# rpiz_test.net
KiCad netlist of a schematic drawn in EAGLE
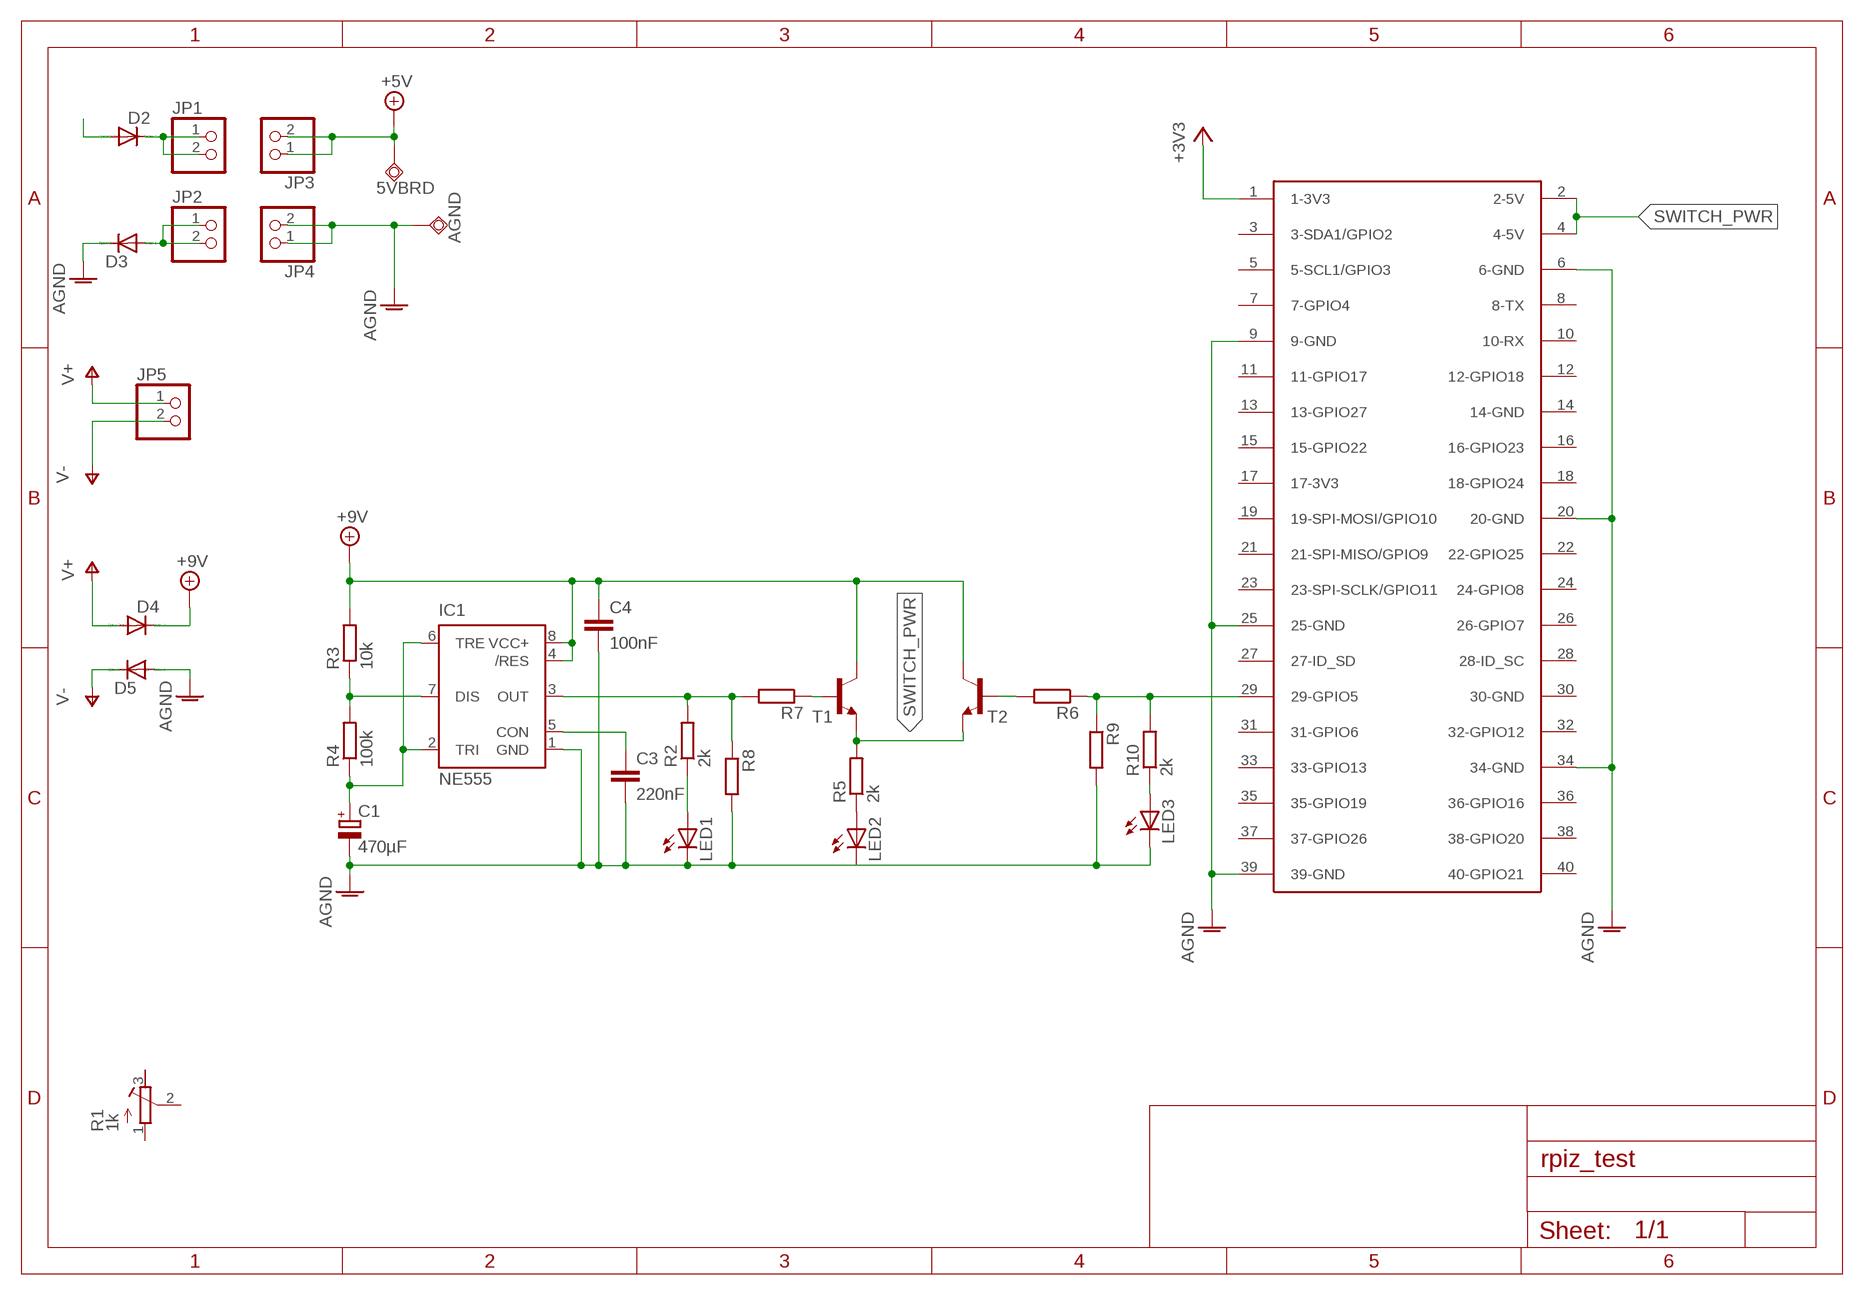
[diagram p0: schematic, sheet 1]

(export (version "E")
  (design (tool "Eeschema 10.0.6"))
  (components
    (comp (ref "5VBRD")
      (value "TPSQTP20SQ")
      (footprint "eagle-import:TP20SQ")
      (libsource (lib "eagle-import") (part "TPSQTP20SQ"))
    )
    (comp (ref "AGND")
      (value "TPSQTP20SQ")
      (footprint "eagle-import:TP20SQ")
      (libsource (lib "eagle-import") (part "TPSQTP20SQ"))
    )
    (comp (ref "C1")
      (value "470µF")
      (footprint "eagle-import:E5-10,5")
      (libsource (lib "eagle-import") (part "CPOL-EUE5-10.5"))
    )
    (comp (ref "C3")
      (value "220nF")
      (footprint "eagle-import:C050-030X075")
      (libsource (lib "eagle-import") (part "C-EU050-030X075"))
    )
    (comp (ref "C4")
      (value "100nF")
      (footprint "eagle-import:C050-030X075")
      (libsource (lib "eagle-import") (part "C-EU050-030X075"))
    )
    (comp (ref "D2")
      (value "1N4148DO35-7")
      (footprint "eagle-import:DO35-7")
      (libsource (lib "eagle-import") (part "1N4148DO35-7"))
    )
    (comp (ref "D3")
      (value "1N4148DO35-7")
      (footprint "eagle-import:DO35-7")
      (libsource (lib "eagle-import") (part "1N4148DO35-7"))
    )
    (comp (ref "D4")
      (value "1N4148DO35-7")
      (footprint "eagle-import:DO35-7")
      (libsource (lib "eagle-import") (part "1N4148DO35-7"))
    )
    (comp (ref "D5")
      (value "1N4148DO35-7")
      (footprint "eagle-import:DO35-7")
      (libsource (lib "eagle-import") (part "1N4148DO35-7"))
    )
    (comp (ref "IC1")
      (value "NE555")
      (footprint "eagle-import:DIL-08")
      (fields (field (name "MF") "Arrow Electronics") (field (name "MPN") "NE555N"))
      (libsource (lib "eagle-import") (part "NE555"))
    )
    (comp (ref "JP1")
      (value "PINHD-1X2")
      (footprint "eagle-import:1X02")
      (libsource (lib "eagle-import") (part "PINHD-1X2"))
    )
    (comp (ref "JP2")
      (value "PINHD-1X2")
      (footprint "eagle-import:1X02")
      (libsource (lib "eagle-import") (part "PINHD-1X2"))
    )
    (comp (ref "JP3")
      (value "PINHD-1X2")
      (footprint "eagle-import:1X02")
      (libsource (lib "eagle-import") (part "PINHD-1X2"))
    )
    (comp (ref "JP4")
      (value "PINHD-1X2")
      (footprint "eagle-import:1X02")
      (libsource (lib "eagle-import") (part "PINHD-1X2"))
    )
    (comp (ref "JP5")
      (value "PINHD-1X2")
      (footprint "eagle-import:1X02")
      (libsource (lib "eagle-import") (part "PINHD-1X2"))
    )
    (comp (ref "LED1")
      (value "LED5MM")
      (footprint "eagle-import:LED5MM")
      (libsource (lib "eagle-import") (part "LED5MM"))
    )
    (comp (ref "LED2")
      (value "LED5MM")
      (footprint "eagle-import:LED5MM")
      (libsource (lib "eagle-import") (part "LED5MM"))
    )
    (comp (ref "LED3")
      (value "LED5MM")
      (footprint "eagle-import:LED5MM")
      (libsource (lib "eagle-import") (part "LED5MM"))
    )
    (comp (ref "R1")
      (value "1k")
      (footprint "eagle-import:RTRIM64W")
      (libsource (lib "eagle-import") (part "R-TRIMM64W"))
    )
    (comp (ref "R2")
      (value "2k")
      (footprint "eagle-import:0207_10")
      (libsource (lib "eagle-import") (part "R-EU_0207/10"))
    )
    (comp (ref "R3")
      (value "10k")
      (footprint "eagle-import:0207_10")
      (libsource (lib "eagle-import") (part "R-EU_0207/10"))
    )
    (comp (ref "R4")
      (value "100k")
      (footprint "eagle-import:0207_10")
      (libsource (lib "eagle-import") (part "R-EU_0207/10"))
    )
    (comp (ref "R5")
      (value "2k")
      (footprint "eagle-import:0207_10")
      (libsource (lib "eagle-import") (part "R-EU_0207/10"))
    )
    (comp (ref "R6")
      (value "R-EU_R0805")
      (footprint "eagle-import:R0805")
      (libsource (lib "eagle-import") (part "R-EU_R0805"))
    )
    (comp (ref "R7")
      (value "R-EU_R0805")
      (footprint "eagle-import:R0805")
      (libsource (lib "eagle-import") (part "R-EU_R0805"))
    )
    (comp (ref "R8")
      (value "R-EU_R0805")
      (footprint "eagle-import:R0805")
      (libsource (lib "eagle-import") (part "R-EU_R0805"))
    )
    (comp (ref "R9")
      (value "R-EU_R0805")
      (footprint "eagle-import:R0805")
      (libsource (lib "eagle-import") (part "R-EU_R0805"))
    )
    (comp (ref "R10")
      (value "2k")
      (footprint "eagle-import:0207_10")
      (libsource (lib "eagle-import") (part "R-EU_0207/10"))
    )
    (comp (ref "T1")
      (value "BC547-NPN-TO92-CBE")
      (footprint "eagle-import:TO92-CBE")
      (libsource (lib "eagle-import") (part "-NPN-TO92-CBEBC547"))
    )
    (comp (ref "T2")
      (value "BC547-NPN-TO92-CBE")
      (footprint "eagle-import:TO92-CBE")
      (libsource (lib "eagle-import") (part "-NPN-TO92-CBEBC547"))
    )
    (comp (ref "U$1")
      (value "RASPBERRY-PI+PIZERO")
      (footprint "eagle-import:RASPBERRY-PI-ZERO")
      (libsource (lib "eagle-import") (part "RASPBERRY-PI+PIZERO"))
    )
  )
  (nets
    (net (code "1") (name "+3V3") (class "Default")
      (node (ref "U$1") (pin "1") (pinfunction "1-3V3_1") (pintype "bidirectional"))
    )
    (net (code "2") (name "+5V") (class "Default")
      (node (ref "5VBRD") (pin "TP") (pinfunction "TP_TP") (pintype "input"))
      (node (ref "JP3") (pin "1") (pinfunction "1_1") (pintype "passive"))
      (node (ref "JP3") (pin "2") (pinfunction "2_2") (pintype "passive"))
    )
    (net (code "3") (name "+9V") (class "Default")
      (node (ref "C4") (pin "1") (pinfunction "1_1") (pintype "passive"))
      (node (ref "D4") (pin "C") (pinfunction "C_C") (pintype "passive"))
      (node (ref "IC1") (pin "4") (pinfunction "/RES_4") (pintype "input"))
      (node (ref "IC1") (pin "8") (pinfunction "VCC+_8") (pintype "power_in"))
      (node (ref "R3") (pin "2") (pinfunction "2_2") (pintype "passive"))
      (node (ref "T1") (pin "C") (pinfunction "C_C") (pintype "passive"))
      (node (ref "T2") (pin "C") (pinfunction "C_C") (pintype "passive"))
    )
    (net (code "4") (name "AGND") (class "Default")
      (node (ref "AGND") (pin "TP") (pinfunction "TP_TP") (pintype "input"))
      (node (ref "C1") (pin "-") (pinfunction "-_-") (pintype "passive"))
      (node (ref "C3") (pin "2") (pinfunction "2_2") (pintype "passive"))
      (node (ref "C4") (pin "2") (pinfunction "2_2") (pintype "passive"))
      (node (ref "D3") (pin "C") (pinfunction "C_C") (pintype "passive"))
      (node (ref "D5") (pin "A") (pinfunction "A_A") (pintype "passive"))
      (node (ref "IC1") (pin "1") (pinfunction "GND_1") (pintype "power_in"))
      (node (ref "JP4") (pin "1") (pinfunction "1_1") (pintype "passive"))
      (node (ref "JP4") (pin "2") (pinfunction "2_2") (pintype "passive"))
      (node (ref "LED1") (pin "K") (pinfunction "C_K") (pintype "passive"))
      (node (ref "LED2") (pin "K") (pinfunction "C_K") (pintype "passive"))
      (node (ref "LED3") (pin "K") (pinfunction "C_K") (pintype "passive"))
      (node (ref "R8") (pin "2") (pinfunction "2_2") (pintype "passive"))
      (node (ref "R9") (pin "2") (pinfunction "2_2") (pintype "passive"))
      (node (ref "U$1") (pin "20") (pinfunction "20-GND_20") (pintype "bidirectional"))
      (node (ref "U$1") (pin "25") (pinfunction "25-GND_25") (pintype "bidirectional"))
      (node (ref "U$1") (pin "34") (pinfunction "34-GND_34") (pintype "bidirectional"))
      (node (ref "U$1") (pin "39") (pinfunction "39-GND_39") (pintype "bidirectional"))
      (node (ref "U$1") (pin "6") (pinfunction "6-GND_6") (pintype "bidirectional"))
      (node (ref "U$1") (pin "9") (pinfunction "9-GND_9") (pintype "bidirectional"))
    )
    (net (code "5") (name "Net-(D2-PadC)") (class "Default")
      (node (ref "D2") (pin "C") (pinfunction "C_C") (pintype "passive"))
      (node (ref "JP1") (pin "1") (pinfunction "1_1") (pintype "passive"))
      (node (ref "JP1") (pin "2") (pinfunction "2_2") (pintype "passive"))
    )
    (net (code "6") (name "Net-(D3-PadA)") (class "Default")
      (node (ref "D3") (pin "A") (pinfunction "A_A") (pintype "passive"))
      (node (ref "JP2") (pin "1") (pinfunction "1_1") (pintype "passive"))
      (node (ref "JP2") (pin "2") (pinfunction "2_2") (pintype "passive"))
    )
    (net (code "7") (name "Net-(IC1-CON)") (class "Default")
      (node (ref "C3") (pin "1") (pinfunction "1_1") (pintype "passive"))
      (node (ref "IC1") (pin "5") (pinfunction "CON_5") (pintype "input"))
    )
    (net (code "8") (name "Net-(IC1-DIS)") (class "Default")
      (node (ref "IC1") (pin "7") (pinfunction "DIS_7") (pintype "input"))
      (node (ref "R3") (pin "1") (pinfunction "1_1") (pintype "passive"))
      (node (ref "R4") (pin "2") (pinfunction "2_2") (pintype "passive"))
    )
    (net (code "9") (name "Net-(IC1-OUT)") (class "Default")
      (node (ref "IC1") (pin "3") (pinfunction "OUT_3") (pintype "output"))
      (node (ref "R2") (pin "2") (pinfunction "2_2") (pintype "passive"))
      (node (ref "R7") (pin "2") (pinfunction "2_2") (pintype "passive"))
      (node (ref "R8") (pin "1") (pinfunction "1_1") (pintype "passive"))
    )
    (net (code "10") (name "Net-(IC1-TRE)") (class "Default")
      (node (ref "C1") (pin "+") (pinfunction "+_+") (pintype "passive"))
      (node (ref "IC1") (pin "2") (pinfunction "TRI_2") (pintype "input"))
      (node (ref "IC1") (pin "6") (pinfunction "TRE_6") (pintype "input"))
      (node (ref "R4") (pin "1") (pinfunction "1_1") (pintype "passive"))
    )
    (net (code "11") (name "Net-(LED1-PadA)") (class "Default")
      (node (ref "LED1") (pin "A") (pinfunction "A_A") (pintype "passive"))
      (node (ref "R2") (pin "1") (pinfunction "1_1") (pintype "passive"))
    )
    (net (code "12") (name "Net-(LED2-PadA)") (class "Default")
      (node (ref "LED2") (pin "A") (pinfunction "A_A") (pintype "passive"))
      (node (ref "R5") (pin "1") (pinfunction "1_1") (pintype "passive"))
    )
    (net (code "13") (name "Net-(LED3-PadA)") (class "Default")
      (node (ref "LED3") (pin "A") (pinfunction "A_A") (pintype "passive"))
      (node (ref "R10") (pin "1") (pinfunction "1_1") (pintype "passive"))
    )
    (net (code "14") (name "Net-(R6-Pad2)") (class "Default")
      (node (ref "R6") (pin "2") (pinfunction "2_2") (pintype "passive"))
      (node (ref "T2") (pin "B") (pinfunction "B_B") (pintype "passive"))
    )
    (net (code "15") (name "Net-(R7-Pad1)") (class "Default")
      (node (ref "R7") (pin "1") (pinfunction "1_1") (pintype "passive"))
      (node (ref "T1") (pin "B") (pinfunction "B_B") (pintype "passive"))
    )
    (net (code "16") (name "Net-(U$1-29-GPIO5)") (class "Default")
      (node (ref "R10") (pin "2") (pinfunction "2_2") (pintype "passive"))
      (node (ref "R6") (pin "1") (pinfunction "1_1") (pintype "passive"))
      (node (ref "R9") (pin "1") (pinfunction "1_1") (pintype "passive"))
      (node (ref "U$1") (pin "29") (pinfunction "29-GPIO5_29") (pintype "bidirectional"))
    )
    (net (code "17") (name "SWITCH_PWR") (class "Default")
      (node (ref "R5") (pin "2") (pinfunction "2_2") (pintype "passive"))
      (node (ref "T1") (pin "E") (pinfunction "E_E") (pintype "passive"))
      (node (ref "T2") (pin "E") (pinfunction "E_E") (pintype "passive"))
      (node (ref "U$1") (pin "2") (pinfunction "2-5V_2") (pintype "bidirectional"))
      (node (ref "U$1") (pin "4") (pinfunction "4-5V_4") (pintype "bidirectional"))
    )
    (net (code "18") (name "V+") (class "Default")
      (node (ref "D4") (pin "A") (pinfunction "A_A") (pintype "passive"))
      (node (ref "JP5") (pin "1") (pinfunction "1_1") (pintype "passive"))
    )
    (net (code "19") (name "V-") (class "Default")
      (node (ref "D5") (pin "C") (pinfunction "C_C") (pintype "passive"))
      (node (ref "JP5") (pin "2") (pinfunction "2_2") (pintype "passive"))
    )
    (net (code "20") (name "unconnected-(D2-PadA)") (class "Default")
      (node (ref "D2") (pin "A") (pinfunction "A_A") (pintype "passive"))
    )
    (net (code "21") (name "unconnected-(R1-A-Pad1)") (class "Default")
      (node (ref "R1") (pin "1") (pinfunction "A_1") (pintype "passive"))
    )
    (net (code "22") (name "unconnected-(R1-E-Pad3)") (class "Default")
      (node (ref "R1") (pin "3") (pinfunction "E_3") (pintype "passive"))
    )
    (net (code "23") (name "unconnected-(R1-S-Pad2)") (class "Default")
      (node (ref "R1") (pin "2") (pinfunction "S_2") (pintype "passive"))
    )
    (net (code "24") (name "unconnected-(U$1-3-SDA1{slash}GPIO2-Pad3)") (class "Default")
      (node (ref "U$1") (pin "3") (pinfunction "3-SDA1/GPIO2_3") (pintype "bidirectional"))
    )
    (net (code "25") (name "unconnected-(U$1-5-SCL1{slash}GPIO3-Pad5)") (class "Default")
      (node (ref "U$1") (pin "5") (pinfunction "5-SCL1/GPIO3_5") (pintype "bidirectional"))
    )
    (net (code "26") (name "unconnected-(U$1-7-GPIO4-Pad7)") (class "Default")
      (node (ref "U$1") (pin "7") (pinfunction "7-GPIO4_7") (pintype "bidirectional"))
    )
    (net (code "27") (name "unconnected-(U$1-8-TX-Pad8)") (class "Default")
      (node (ref "U$1") (pin "8") (pinfunction "8-TX_8") (pintype "bidirectional"))
    )
    (net (code "28") (name "unconnected-(U$1-10-RX-Pad10)") (class "Default")
      (node (ref "U$1") (pin "10") (pinfunction "10-RX_10") (pintype "bidirectional"))
    )
    (net (code "29") (name "unconnected-(U$1-11-GPIO17-Pad11)") (class "Default")
      (node (ref "U$1") (pin "11") (pinfunction "11-GPIO17_11") (pintype "bidirectional"))
    )
    (net (code "30") (name "unconnected-(U$1-12-GPIO18-Pad12)") (class "Default")
      (node (ref "U$1") (pin "12") (pinfunction "12-GPIO18_12") (pintype "bidirectional"))
    )
    (net (code "31") (name "unconnected-(U$1-13-GPIO27-Pad13)") (class "Default")
      (node (ref "U$1") (pin "13") (pinfunction "13-GPIO27_13") (pintype "bidirectional"))
    )
    (net (code "32") (name "unconnected-(U$1-14-GND-Pad14)") (class "Default")
      (node (ref "U$1") (pin "14") (pinfunction "14-GND_14") (pintype "bidirectional"))
    )
    (net (code "33") (name "unconnected-(U$1-15-GPIO22-Pad15)") (class "Default")
      (node (ref "U$1") (pin "15") (pinfunction "15-GPIO22_15") (pintype "bidirectional"))
    )
    (net (code "34") (name "unconnected-(U$1-16-GPIO23-Pad16)") (class "Default")
      (node (ref "U$1") (pin "16") (pinfunction "16-GPIO23_16") (pintype "bidirectional"))
    )
    (net (code "35") (name "unconnected-(U$1-17-3V3-Pad17)") (class "Default")
      (node (ref "U$1") (pin "17") (pinfunction "17-3V3_17") (pintype "bidirectional"))
    )
    (net (code "36") (name "unconnected-(U$1-18-GPIO24-Pad18)") (class "Default")
      (node (ref "U$1") (pin "18") (pinfunction "18-GPIO24_18") (pintype "bidirectional"))
    )
    (net (code "37") (name "unconnected-(U$1-19-SPI-MOSI{slash}GPIO10-Pad19)") (class "Default")
      (node (ref "U$1") (pin "19") (pinfunction "19-SPI-MOSI/GPIO10_19") (pintype "bidirectional"))
    )
    (net (code "38") (name "unconnected-(U$1-21-SPI-MISO{slash}GPIO9-Pad21)") (class "Default")
      (node (ref "U$1") (pin "21") (pinfunction "21-SPI-MISO/GPIO9_21") (pintype "bidirectional"))
    )
    (net (code "39") (name "unconnected-(U$1-22-GPIO25-Pad22)") (class "Default")
      (node (ref "U$1") (pin "22") (pinfunction "22-GPIO25_22") (pintype "bidirectional"))
    )
    (net (code "40") (name "unconnected-(U$1-23-SPI-SCLK{slash}GPIO11-Pad23)") (class "Default")
      (node (ref "U$1") (pin "23") (pinfunction "23-SPI-SCLK/GPIO11_23") (pintype "bidirectional"))
    )
    (net (code "41") (name "unconnected-(U$1-24-GPIO8-Pad24)") (class "Default")
      (node (ref "U$1") (pin "24") (pinfunction "24-GPIO8_24") (pintype "bidirectional"))
    )
    (net (code "42") (name "unconnected-(U$1-26-GPIO7-Pad26)") (class "Default")
      (node (ref "U$1") (pin "26") (pinfunction "26-GPIO7_26") (pintype "bidirectional"))
    )
    (net (code "43") (name "unconnected-(U$1-27-ID_SD-Pad27)") (class "Default")
      (node (ref "U$1") (pin "27") (pinfunction "27-ID_SD_27") (pintype "bidirectional"))
    )
    (net (code "44") (name "unconnected-(U$1-28-ID_SC-Pad28)") (class "Default")
      (node (ref "U$1") (pin "28") (pinfunction "28-ID_SC_28") (pintype "bidirectional"))
    )
    (net (code "45") (name "unconnected-(U$1-30-GND-Pad30)") (class "Default")
      (node (ref "U$1") (pin "30") (pinfunction "30-GND_30") (pintype "bidirectional"))
    )
    (net (code "46") (name "unconnected-(U$1-31-GPIO6-Pad31)") (class "Default")
      (node (ref "U$1") (pin "31") (pinfunction "31-GPIO6_31") (pintype "bidirectional"))
    )
    (net (code "47") (name "unconnected-(U$1-32-GPIO12-Pad32)") (class "Default")
      (node (ref "U$1") (pin "32") (pinfunction "32-GPIO12_32") (pintype "bidirectional"))
    )
    (net (code "48") (name "unconnected-(U$1-33-GPIO13-Pad33)") (class "Default")
      (node (ref "U$1") (pin "33") (pinfunction "33-GPIO13_33") (pintype "bidirectional"))
    )
    (net (code "49") (name "unconnected-(U$1-35-GPIO19-Pad35)") (class "Default")
      (node (ref "U$1") (pin "35") (pinfunction "35-GPIO19_35") (pintype "bidirectional"))
    )
    (net (code "50") (name "unconnected-(U$1-36-GPIO16-Pad36)") (class "Default")
      (node (ref "U$1") (pin "36") (pinfunction "36-GPIO16_36") (pintype "bidirectional"))
    )
    (net (code "51") (name "unconnected-(U$1-37-GPIO26-Pad37)") (class "Default")
      (node (ref "U$1") (pin "37") (pinfunction "37-GPIO26_37") (pintype "bidirectional"))
    )
    (net (code "52") (name "unconnected-(U$1-38-GPIO20-Pad38)") (class "Default")
      (node (ref "U$1") (pin "38") (pinfunction "38-GPIO20_38") (pintype "bidirectional"))
    )
    (net (code "53") (name "unconnected-(U$1-40-GPIO21-Pad40)") (class "Default")
      (node (ref "U$1") (pin "40") (pinfunction "40-GPIO21_40") (pintype "bidirectional"))
    )
  )
)
